# 150110_AriloTX_REV3_1_0_868MHZ_CORRECT_T.net
KiCad netlist of a schematic drawn in EAGLE
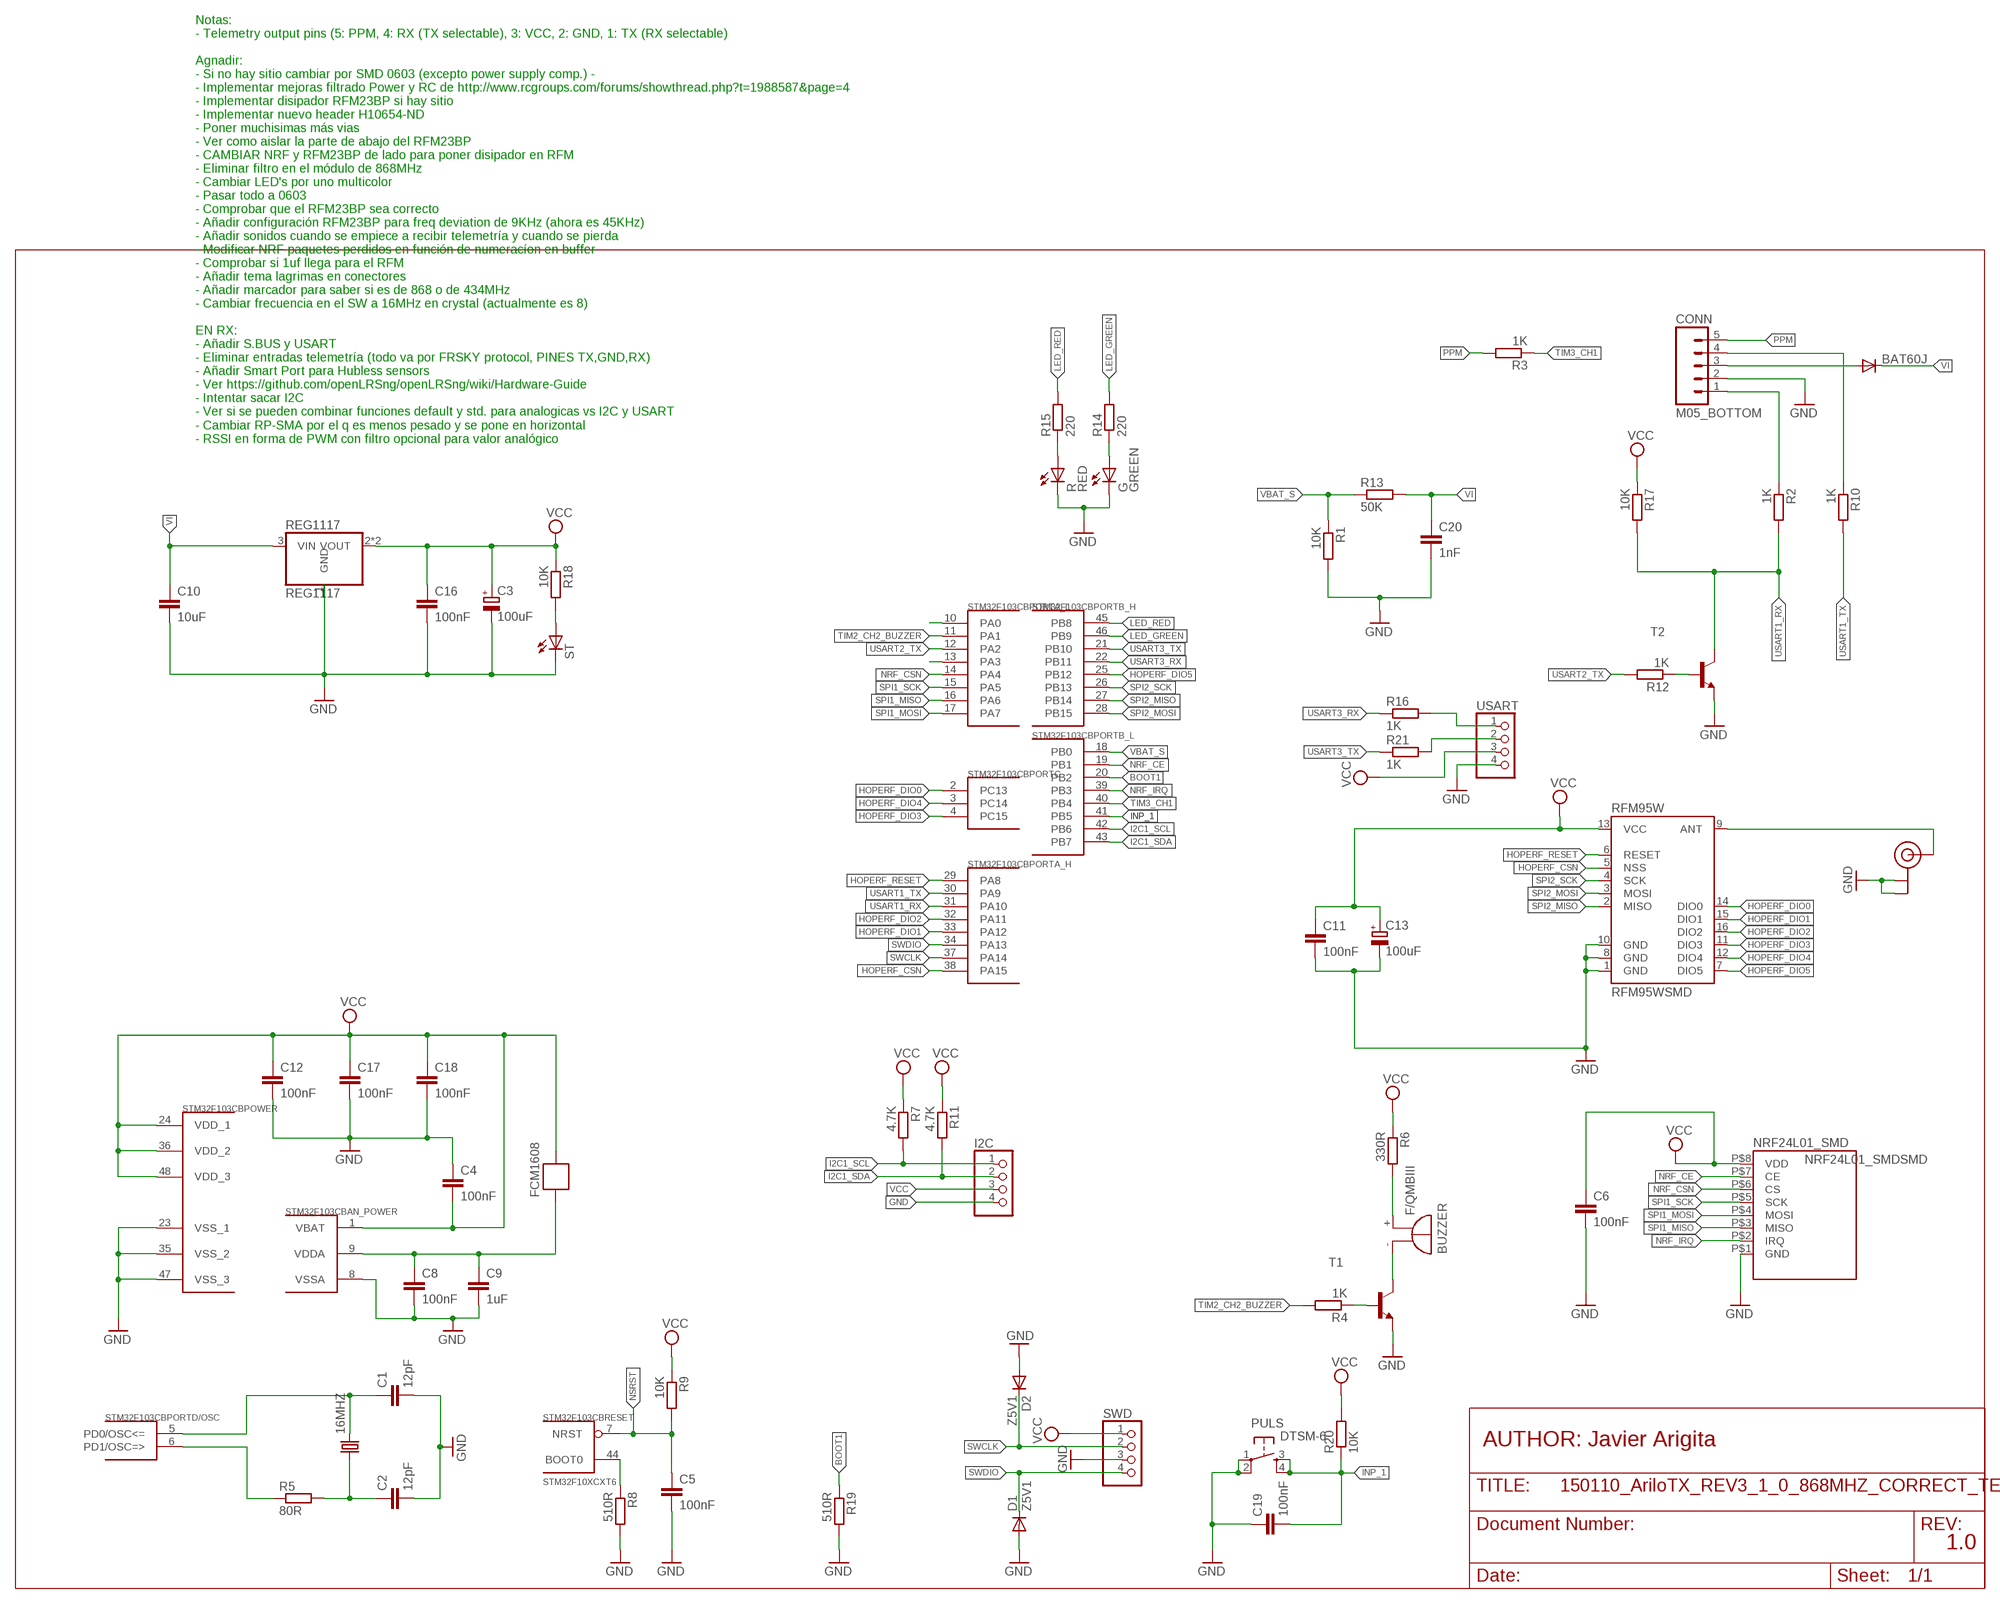
[diagram p0: schematic, sheet 1]

(export (version "E")
  (design (tool "Eeschema 10.0.6"))
  (components
    (comp (ref "16MHZ")
      (value "CRYSTAL5X3")
      (footprint "eagle-import:CRYSTAL-SMD-5X3")
      (libsource (lib "eagle-import") (part "CRYSTAL5X3"))
    )
    (comp (ref "BAT60J")
      (value "DIODE-SOD323-R")
      (footprint "eagle-import:SOD323-R")
      (libsource (lib "eagle-import") (part "DIODE-SOD323-R"))
    )
    (comp (ref "BUZZER")
      (value "F/QMBIII")
      (footprint "eagle-import:F_QMBIII")
      (libsource (lib "eagle-import") (part "F/QMBIII"))
    )
    (comp (ref "C1")
      (value "12pF")
      (footprint "eagle-import:C0603")
      (libsource (lib "eagle-import") (part "C-EUC0603"))
    )
    (comp (ref "C2")
      (value "12pF")
      (footprint "eagle-import:C0603")
      (libsource (lib "eagle-import") (part "C-EUC0603"))
    )
    (comp (ref "C3")
      (value "100uF")
      (footprint "eagle-import:SMC_B")
      (libsource (lib "eagle-import") (part "CPOL-EUSMCB"))
    )
    (comp (ref "C4")
      (value "100nF")
      (footprint "eagle-import:C0603")
      (libsource (lib "eagle-import") (part "C-EUC0603"))
    )
    (comp (ref "C5")
      (value "100nF")
      (footprint "eagle-import:C0603")
      (libsource (lib "eagle-import") (part "C-EUC0603"))
    )
    (comp (ref "C6")
      (value "100nF")
      (footprint "eagle-import:C0603")
      (libsource (lib "eagle-import") (part "C-EUC0603"))
    )
    (comp (ref "C8")
      (value "100nF")
      (footprint "eagle-import:C0603")
      (libsource (lib "eagle-import") (part "C-EUC0603"))
    )
    (comp (ref "C9")
      (value "1uF")
      (footprint "eagle-import:C0603")
      (libsource (lib "eagle-import") (part "C-EUC0603"))
    )
    (comp (ref "C10")
      (value "10uF")
      (footprint "eagle-import:C3216")
      (libsource (lib "eagle-import") (part "resistor_C-EUC3216"))
    )
    (comp (ref "C11")
      (value "100nF")
      (footprint "eagle-import:C0603")
      (libsource (lib "eagle-import") (part "C-EUC0603"))
    )
    (comp (ref "C12")
      (value "100nF")
      (footprint "eagle-import:C0603")
      (libsource (lib "eagle-import") (part "C-EUC0603"))
    )
    (comp (ref "C13")
      (value "100uF")
      (footprint "eagle-import:SMC_B")
      (libsource (lib "eagle-import") (part "CPOL-EUSMCB"))
    )
    (comp (ref "C16")
      (value "100nF")
      (footprint "eagle-import:C0603")
      (libsource (lib "eagle-import") (part "C-EUC0603"))
    )
    (comp (ref "C17")
      (value "100nF")
      (footprint "eagle-import:C0603")
      (libsource (lib "eagle-import") (part "C-EUC0603"))
    )
    (comp (ref "C18")
      (value "100nF")
      (footprint "eagle-import:C0603")
      (libsource (lib "eagle-import") (part "C-EUC0603"))
    )
    (comp (ref "C19")
      (value "100nF")
      (footprint "eagle-import:C0603")
      (libsource (lib "eagle-import") (part "C-EUC0603"))
    )
    (comp (ref "C20")
      (value "1nF")
      (footprint "eagle-import:C0603")
      (libsource (lib "eagle-import") (part "C-EUC0603"))
    )
    (comp (ref "CONN")
      (value "M05_BOTTOM")
      (footprint "eagle-import:M05_BOTTOM")
      (libsource (lib "eagle-import") (part "M05_BOTTOM"))
    )
    (comp (ref "D1")
      (value "Z5V1")
      (footprint "eagle-import:SOD323-R")
      (libsource (lib "eagle-import") (part "DIODE-SOD323-R"))
    )
    (comp (ref "D2")
      (value "Z5V1")
      (footprint "eagle-import:SOD323-R")
      (libsource (lib "eagle-import") (part "DIODE-SOD323-R"))
    )
    (comp (ref "FCM1608")
      (value "FERRITE-BEAD")
      (footprint "eagle-import:R0603")
      (libsource (lib "eagle-import") (part "FERRITE-BEAD"))
    )
    (comp (ref "G")
      (value "GREEN")
      (footprint "eagle-import:CHIP-LED0603")
      (libsource (lib "eagle-import") (part "LEDCHIP-LED0603"))
    )
    (comp (ref "I2C")
      (value "PINHD-1X4")
      (footprint "eagle-import:1X04")
      (libsource (lib "eagle-import") (part "PINHD-1X4"))
    )
    (comp (ref "NRF24L01_SMD")
      (value "NRF24L01_SMDSMD")
      (footprint "eagle-import:NRF24L01_SMD")
      (libsource (lib "eagle-import") (part "NRF24L01_SMDSMD"))
    )
    (comp (ref "PULS")
      (value "DTSM-6")
      (footprint "eagle-import:DTSM-6")
      (libsource (lib "eagle-import") (part "DTSM-6"))
    )
    (comp (ref "R")
      (value "RED")
      (footprint "eagle-import:CHIP-LED0603")
      (libsource (lib "eagle-import") (part "LEDCHIP-LED0603"))
    )
    (comp (ref "R1")
      (value "10K")
      (footprint "eagle-import:R0603")
      (libsource (lib "eagle-import") (part "R-EU_R0603"))
    )
    (comp (ref "R2")
      (value "1K")
      (footprint "eagle-import:R0603")
      (libsource (lib "eagle-import") (part "R-EU_R0603"))
    )
    (comp (ref "R3")
      (value "1K")
      (footprint "eagle-import:R0603")
      (libsource (lib "eagle-import") (part "R-EU_R0603"))
    )
    (comp (ref "R4")
      (value "1K")
      (footprint "eagle-import:R0603")
      (libsource (lib "eagle-import") (part "R-EU_R0603"))
    )
    (comp (ref "R5")
      (value "80R")
      (footprint "eagle-import:R0603")
      (libsource (lib "eagle-import") (part "R-EU_R0603"))
    )
    (comp (ref "R6")
      (value "330R")
      (footprint "eagle-import:R0603")
      (libsource (lib "eagle-import") (part "R-EU_R0603"))
    )
    (comp (ref "R7")
      (value "4.7K")
      (footprint "eagle-import:R0603")
      (libsource (lib "eagle-import") (part "R-EU_R0603"))
    )
    (comp (ref "R8")
      (value "510R")
      (footprint "eagle-import:R0603")
      (libsource (lib "eagle-import") (part "R-EU_R0603"))
    )
    (comp (ref "R9")
      (value "10K")
      (footprint "eagle-import:R0603")
      (libsource (lib "eagle-import") (part "R-EU_R0603"))
    )
    (comp (ref "R10")
      (value "1K")
      (footprint "eagle-import:R0603")
      (libsource (lib "eagle-import") (part "R-EU_R0603"))
    )
    (comp (ref "R11")
      (value "4.7K")
      (footprint "eagle-import:R0603")
      (libsource (lib "eagle-import") (part "R-EU_R0603"))
    )
    (comp (ref "R12")
      (value "1K")
      (footprint "eagle-import:R0603")
      (libsource (lib "eagle-import") (part "R-EU_R0603"))
    )
    (comp (ref "R13")
      (value "50K")
      (footprint "eagle-import:R0603")
      (libsource (lib "eagle-import") (part "R-EU_R0603"))
    )
    (comp (ref "R14")
      (value "220")
      (footprint "eagle-import:R0603")
      (libsource (lib "eagle-import") (part "R-EU_R0603"))
    )
    (comp (ref "R15")
      (value "220")
      (footprint "eagle-import:R0603")
      (libsource (lib "eagle-import") (part "R-EU_R0603"))
    )
    (comp (ref "R16")
      (value "1K")
      (footprint "eagle-import:R0603")
      (libsource (lib "eagle-import") (part "R-EU_R0603"))
    )
    (comp (ref "R17")
      (value "10K")
      (footprint "eagle-import:R0603")
      (libsource (lib "eagle-import") (part "R-EU_R0603"))
    )
    (comp (ref "R18")
      (value "10K")
      (footprint "eagle-import:R0603")
      (libsource (lib "eagle-import") (part "R-EU_R0603"))
    )
    (comp (ref "R19")
      (value "510R")
      (footprint "eagle-import:R0603")
      (libsource (lib "eagle-import") (part "R-EU_R0603"))
    )
    (comp (ref "R20")
      (value "10K")
      (footprint "eagle-import:R0603")
      (libsource (lib "eagle-import") (part "R-EU_R0603"))
    )
    (comp (ref "R21")
      (value "1K")
      (footprint "eagle-import:R0603")
      (libsource (lib "eagle-import") (part "R-EU_R0603"))
    )
    (comp (ref "REG1117")
      (value "REG1117")
      (footprint "eagle-import:SOT223")
      (libsource (lib "eagle-import") (part "REG1117"))
    )
    (comp (ref "RFM95W")
      (value "RFM95WSMD")
      (footprint "eagle-import:MISIEK_RFM95W_SMD")
      (libsource (lib "eagle-import") (part "MISIEK_RFM95WSMD"))
    )
    (comp (ref "ST")
      (value "LEDCHIP-LED0603")
      (footprint "eagle-import:CHIP-LED0603")
      (libsource (lib "eagle-import") (part "LEDCHIP-LED0603"))
    )
    (comp (ref "STM32F103CB")
      (value "STM32F10XCXT6")
      (footprint "eagle-import:TQFP48")
      (libsource (lib "eagle-import") (part "STM32F10XCXT6"))
    )
    (comp (ref "SWD")
      (value "PINHD-1X4")
      (footprint "eagle-import:1X04")
      (libsource (lib "eagle-import") (part "PINHD-1X4"))
    )
    (comp (ref "T1")
      (value "BC848-NPN-SOT23-BEC")
      (footprint "eagle-import:SOT23-BEC")
      (libsource (lib "eagle-import") (part "-NPN-SOT23-BECBC848"))
    )
    (comp (ref "T2")
      (value "BC848-NPN-SOT23-BEC")
      (footprint "eagle-import:SOT23-BEC")
      (libsource (lib "eagle-import") (part "-NPN-SOT23-BECBC848"))
    )
    (comp (ref "U.FL")
      (value "U.FL")
      (footprint "eagle-import:U.FL")
      (libsource (lib "eagle-import") (part "U.FL"))
    )
    (comp (ref "USART")
      (value "PINHD-1X4")
      (footprint "eagle-import:1X04")
      (libsource (lib "eagle-import") (part "PINHD-1X4"))
    )
  )
  (nets
    (net (code "1") (name "BOOT1") (class "Default")
      (node (ref "R19") (pin "1") (pinfunction "1_1") (pintype "passive"))
      (node (ref "STM32F103CB") (pin "20") (pinfunction "PB2_20") (pintype "bidirectional"))
    )
    (net (code "2") (name "GND") (class "Default")
      (node (ref "C1") (pin "2") (pinfunction "2_2") (pintype "passive"))
      (node (ref "C10") (pin "2") (pinfunction "2_2") (pintype "passive"))
      (node (ref "C11") (pin "2") (pinfunction "2_2") (pintype "passive"))
      (node (ref "C12") (pin "2") (pinfunction "2_2") (pintype "passive"))
      (node (ref "C13") (pin "-") (pinfunction "-_-") (pintype "passive"))
      (node (ref "C16") (pin "2") (pinfunction "2_2") (pintype "passive"))
      (node (ref "C17") (pin "2") (pinfunction "2_2") (pintype "passive"))
      (node (ref "C18") (pin "2") (pinfunction "2_2") (pintype "passive"))
      (node (ref "C19") (pin "1") (pinfunction "1_1") (pintype "passive"))
      (node (ref "C2") (pin "2") (pinfunction "2_2") (pintype "passive"))
      (node (ref "C20") (pin "2") (pinfunction "2_2") (pintype "passive"))
      (node (ref "C3") (pin "-") (pinfunction "-_-") (pintype "passive"))
      (node (ref "C4") (pin "1") (pinfunction "1_1") (pintype "passive"))
      (node (ref "C5") (pin "2") (pinfunction "2_2") (pintype "passive"))
      (node (ref "C6") (pin "2") (pinfunction "2_2") (pintype "passive"))
      (node (ref "C8") (pin "2") (pinfunction "2_2") (pintype "passive"))
      (node (ref "C9") (pin "2") (pinfunction "2_2") (pintype "passive"))
      (node (ref "CONN") (pin "2") (pinfunction "2_2") (pintype "passive"))
      (node (ref "D1") (pin "A") (pinfunction "A_A") (pintype "passive"))
      (node (ref "D2") (pin "A") (pinfunction "A_A") (pintype "passive"))
      (node (ref "G") (pin "C") (pinfunction "C_C") (pintype "passive"))
      (node (ref "I2C") (pin "4") (pinfunction "4_4") (pintype "passive"))
      (node (ref "NRF24L01_SMD") (pin "P$1") (pinfunction "GND_P$1") (pintype "power_in"))
      (node (ref "PULS") (pin "1") (pinfunction "1_1") (pintype "passive"))
      (node (ref "PULS") (pin "2") (pinfunction "2_2") (pintype "passive"))
      (node (ref "R") (pin "C") (pinfunction "C_C") (pintype "passive"))
      (node (ref "R1") (pin "2") (pinfunction "2_2") (pintype "passive"))
      (node (ref "R19") (pin "2") (pinfunction "2_2") (pintype "passive"))
      (node (ref "R8") (pin "2") (pinfunction "2_2") (pintype "passive"))
      (node (ref "REG1117") (pin "1") (pinfunction "GND_1") (pintype "power_in"))
      (node (ref "RFM95W") (pin "1") (pinfunction "GND_1") (pintype "power_in"))
      (node (ref "RFM95W") (pin "10") (pinfunction "GND_10") (pintype "power_in"))
      (node (ref "RFM95W") (pin "8") (pinfunction "GND_8") (pintype "power_in"))
      (node (ref "ST") (pin "C") (pinfunction "C_C") (pintype "passive"))
      (node (ref "STM32F103CB") (pin "23") (pinfunction "VSS_1_23") (pintype "power_in"))
      (node (ref "STM32F103CB") (pin "35") (pinfunction "VSS_2_35") (pintype "power_in"))
      (node (ref "STM32F103CB") (pin "47") (pinfunction "VSS_3_47") (pintype "power_in"))
      (node (ref "STM32F103CB") (pin "8") (pinfunction "VSSA_8") (pintype "power_in"))
      (node (ref "SWD") (pin "3") (pinfunction "3_3") (pintype "passive"))
      (node (ref "T1") (pin "E") (pinfunction "E_E") (pintype "passive"))
      (node (ref "T2") (pin "E") (pinfunction "E_E") (pintype "passive"))
      (node (ref "U.FL") (pin "P$1") (pinfunction "GND_P$1") (pintype "bidirectional"))
      (node (ref "U.FL") (pin "P$2") (pinfunction "GND_P$2") (pintype "bidirectional"))
      (node (ref "USART") (pin "4") (pinfunction "4_4") (pintype "passive"))
    )
    (net (code "3") (name "HOPERF_CSN") (class "Default")
      (node (ref "RFM95W") (pin "5") (pinfunction "NSS_5") (pintype "input"))
      (node (ref "STM32F103CB") (pin "38") (pinfunction "PA15_38") (pintype "bidirectional"))
    )
    (net (code "4") (name "HOPERF_DIO0") (class "Default")
      (node (ref "RFM95W") (pin "14") (pinfunction "DIO0_14") (pintype "input"))
      (node (ref "STM32F103CB") (pin "2") (pinfunction "PC13_2") (pintype "bidirectional"))
    )
    (net (code "5") (name "HOPERF_DIO1") (class "Default")
      (node (ref "RFM95W") (pin "15") (pinfunction "DIO1_15") (pintype "input"))
      (node (ref "STM32F103CB") (pin "33") (pinfunction "PA12_33") (pintype "bidirectional"))
    )
    (net (code "6") (name "HOPERF_DIO2") (class "Default")
      (node (ref "RFM95W") (pin "16") (pinfunction "DIO2_16") (pintype "input"))
      (node (ref "STM32F103CB") (pin "32") (pinfunction "PA11_32") (pintype "bidirectional"))
    )
    (net (code "7") (name "HOPERF_DIO3") (class "Default")
      (node (ref "RFM95W") (pin "11") (pinfunction "DIO3_11") (pintype "bidirectional"))
      (node (ref "STM32F103CB") (pin "4") (pinfunction "PC15_4") (pintype "bidirectional"))
    )
    (net (code "8") (name "HOPERF_DIO4") (class "Default")
      (node (ref "RFM95W") (pin "12") (pinfunction "DIO4_12") (pintype "bidirectional"))
      (node (ref "STM32F103CB") (pin "3") (pinfunction "PC14_3") (pintype "bidirectional"))
    )
    (net (code "9") (name "HOPERF_DIO5") (class "Default")
      (node (ref "RFM95W") (pin "7") (pinfunction "DIO5_7") (pintype "bidirectional"))
      (node (ref "STM32F103CB") (pin "25") (pinfunction "PB12_25") (pintype "bidirectional"))
    )
    (net (code "10") (name "HOPERF_RESET") (class "Default")
      (node (ref "RFM95W") (pin "6") (pinfunction "RESET_6") (pintype "output"))
      (node (ref "STM32F103CB") (pin "29") (pinfunction "PA8_29") (pintype "bidirectional"))
    )
    (net (code "11") (name "I2C1_SCL") (class "Default")
      (node (ref "I2C") (pin "1") (pinfunction "1_1") (pintype "passive"))
      (node (ref "R7") (pin "2") (pinfunction "2_2") (pintype "passive"))
      (node (ref "STM32F103CB") (pin "42") (pinfunction "PB6_42") (pintype "bidirectional"))
    )
    (net (code "12") (name "I2C1_SDA") (class "Default")
      (node (ref "I2C") (pin "2") (pinfunction "2_2") (pintype "passive"))
      (node (ref "R11") (pin "2") (pinfunction "2_2") (pintype "passive"))
      (node (ref "STM32F103CB") (pin "43") (pinfunction "PB7_43") (pintype "bidirectional"))
    )
    (net (code "13") (name "INP_1") (class "Default")
      (node (ref "C19") (pin "2") (pinfunction "2_2") (pintype "passive"))
      (node (ref "PULS") (pin "3") (pinfunction "3_3") (pintype "passive"))
      (node (ref "PULS") (pin "4") (pinfunction "4_4") (pintype "passive"))
      (node (ref "R20") (pin "1") (pinfunction "1_1") (pintype "passive"))
      (node (ref "STM32F103CB") (pin "41") (pinfunction "PB5_41") (pintype "bidirectional"))
    )
    (net (code "14") (name "LED_GREEN") (class "Default")
      (node (ref "R14") (pin "2") (pinfunction "2_2") (pintype "passive"))
      (node (ref "STM32F103CB") (pin "46") (pinfunction "PB9_46") (pintype "bidirectional"))
    )
    (net (code "15") (name "LED_RED") (class "Default")
      (node (ref "R15") (pin "2") (pinfunction "2_2") (pintype "passive"))
      (node (ref "STM32F103CB") (pin "45") (pinfunction "PB8_45") (pintype "bidirectional"))
    )
    (net (code "16") (name "NRF_CE") (class "Default")
      (node (ref "NRF24L01_SMD") (pin "P$7") (pinfunction "CE_P$7") (pintype "input"))
      (node (ref "STM32F103CB") (pin "19") (pinfunction "PB1_19") (pintype "bidirectional"))
    )
    (net (code "17") (name "NRF_CSN") (class "Default")
      (node (ref "NRF24L01_SMD") (pin "P$6") (pinfunction "CS_P$6") (pintype "input"))
      (node (ref "STM32F103CB") (pin "14") (pinfunction "PA4_14") (pintype "bidirectional"))
    )
    (net (code "18") (name "NRF_IRQ") (class "Default")
      (node (ref "NRF24L01_SMD") (pin "P$2") (pinfunction "IRQ_P$2") (pintype "output"))
      (node (ref "STM32F103CB") (pin "39") (pinfunction "PB3_39") (pintype "bidirectional"))
    )
    (net (code "19") (name "NSRST") (class "Default")
      (node (ref "C5") (pin "1") (pinfunction "1_1") (pintype "passive"))
      (node (ref "R9") (pin "2") (pinfunction "2_2") (pintype "passive"))
      (node (ref "STM32F103CB") (pin "7") (pinfunction "NRST_7") (pintype "input"))
    )
    (net (code "20") (name "Net-(16MHZ-2)") (class "Default")
      (node (ref "16MHZ") (pin "3") (pinfunction "2_3") (pintype "passive"))
      (node (ref "C1") (pin "1") (pinfunction "1_1") (pintype "passive"))
      (node (ref "STM32F103CB") (pin "5") (pinfunction "PD0/OSC<=_5") (pintype "bidirectional"))
    )
    (net (code "21") (name "Net-(16MHZ-Pad1)") (class "Default")
      (node (ref "16MHZ") (pin "1") (pinfunction "1_1") (pintype "passive"))
      (node (ref "C2") (pin "1") (pinfunction "1_1") (pintype "passive"))
      (node (ref "R5") (pin "2") (pinfunction "2_2") (pintype "passive"))
    )
    (net (code "22") (name "Net-(BAT60J-PadA)") (class "Default")
      (node (ref "BAT60J") (pin "A") (pinfunction "A_A") (pintype "passive"))
      (node (ref "CONN") (pin "3") (pinfunction "3_3") (pintype "passive"))
    )
    (net (code "23") (name "Net-(BUZZER-+)") (class "Default")
      (node (ref "BUZZER") (pin "-") (pinfunction "+_-") (pintype "passive"))
      (node (ref "T1") (pin "C") (pinfunction "C_C") (pintype "passive"))
    )
    (net (code "24") (name "Net-(BUZZER--)") (class "Default")
      (node (ref "BUZZER") (pin "+") (pinfunction "-_+") (pintype "passive"))
      (node (ref "R6") (pin "2") (pinfunction "2_2") (pintype "passive"))
    )
    (net (code "25") (name "Net-(CONN-Pad1)") (class "Default")
      (node (ref "CONN") (pin "1") (pinfunction "1_1") (pintype "passive"))
      (node (ref "R2") (pin "1") (pinfunction "1_1") (pintype "passive"))
    )
    (net (code "26") (name "Net-(CONN-Pad4)") (class "Default")
      (node (ref "CONN") (pin "4") (pinfunction "4_4") (pintype "passive"))
      (node (ref "R10") (pin "1") (pinfunction "1_1") (pintype "passive"))
    )
    (net (code "27") (name "Net-(FCM1608-P$2)") (class "Default")
      (node (ref "C8") (pin "1") (pinfunction "1_1") (pintype "passive"))
      (node (ref "C9") (pin "1") (pinfunction "1_1") (pintype "passive"))
      (node (ref "FCM1608") (pin "2") (pinfunction "P$2_2") (pintype "bidirectional"))
      (node (ref "STM32F103CB") (pin "9") (pinfunction "VDDA_9") (pintype "power_in"))
    )
    (net (code "28") (name "Net-(G-PadA)") (class "Default")
      (node (ref "G") (pin "A") (pinfunction "A_A") (pintype "passive"))
      (node (ref "R14") (pin "1") (pinfunction "1_1") (pintype "passive"))
    )
    (net (code "29") (name "Net-(R-PadA)") (class "Default")
      (node (ref "R") (pin "A") (pinfunction "A_A") (pintype "passive"))
      (node (ref "R15") (pin "1") (pinfunction "1_1") (pintype "passive"))
    )
    (net (code "30") (name "Net-(R4-Pad1)") (class "Default")
      (node (ref "R4") (pin "1") (pinfunction "1_1") (pintype "passive"))
      (node (ref "T1") (pin "B") (pinfunction "B_B") (pintype "passive"))
    )
    (net (code "31") (name "Net-(R12-Pad1)") (class "Default")
      (node (ref "R12") (pin "1") (pinfunction "1_1") (pintype "passive"))
      (node (ref "T2") (pin "B") (pinfunction "B_B") (pintype "passive"))
    )
    (net (code "32") (name "Net-(R16-Pad2)") (class "Default")
      (node (ref "R16") (pin "2") (pinfunction "2_2") (pintype "passive"))
      (node (ref "USART") (pin "1") (pinfunction "1_1") (pintype "passive"))
    )
    (net (code "33") (name "Net-(R18-Pad2)") (class "Default")
      (node (ref "R18") (pin "2") (pinfunction "2_2") (pintype "passive"))
      (node (ref "ST") (pin "A") (pinfunction "A_A") (pintype "passive"))
    )
    (net (code "34") (name "Net-(R21-Pad2)") (class "Default")
      (node (ref "R21") (pin "2") (pinfunction "2_2") (pintype "passive"))
      (node (ref "USART") (pin "2") (pinfunction "2_2") (pintype "passive"))
    )
    (net (code "35") (name "Net-(RFM95W-ANT)") (class "Default")
      (node (ref "RFM95W") (pin "9") (pinfunction "ANT_9") (pintype "bidirectional"))
      (node (ref "U.FL") (pin "P$3") (pinfunction "SIGNAL_P$3") (pintype "bidirectional"))
    )
    (net (code "36") (name "Net-(STM32F103CBG-PD1{slash}OSC=>)") (class "Default")
      (node (ref "R5") (pin "1") (pinfunction "1_1") (pintype "passive"))
      (node (ref "STM32F103CB") (pin "6") (pinfunction "PD1/OSC=>_6") (pintype "bidirectional"))
    )
    (net (code "37") (name "Net-(STM32F103CBI-BOOT0)") (class "Default")
      (node (ref "R8") (pin "1") (pinfunction "1_1") (pintype "passive"))
      (node (ref "STM32F103CB") (pin "44") (pinfunction "BOOT0_44") (pintype "input"))
    )
    (net (code "38") (name "PPM") (class "Default")
      (node (ref "CONN") (pin "5") (pinfunction "5_5") (pintype "passive"))
      (node (ref "R3") (pin "2") (pinfunction "2_2") (pintype "passive"))
    )
    (net (code "39") (name "SPI1_MISO") (class "Default")
      (node (ref "NRF24L01_SMD") (pin "P$3") (pinfunction "MISO_P$3") (pintype "output"))
      (node (ref "STM32F103CB") (pin "16") (pinfunction "PA6_16") (pintype "bidirectional"))
    )
    (net (code "40") (name "SPI1_MOSI") (class "Default")
      (node (ref "NRF24L01_SMD") (pin "P$4") (pinfunction "MOSI_P$4") (pintype "input"))
      (node (ref "STM32F103CB") (pin "17") (pinfunction "PA7_17") (pintype "bidirectional"))
    )
    (net (code "41") (name "SPI1_SCK") (class "Default")
      (node (ref "NRF24L01_SMD") (pin "P$5") (pinfunction "SCK_P$5") (pintype "input"))
      (node (ref "STM32F103CB") (pin "15") (pinfunction "PA5_15") (pintype "bidirectional"))
    )
    (net (code "42") (name "SPI2_MISO") (class "Default")
      (node (ref "RFM95W") (pin "2") (pinfunction "MISO_2") (pintype "output"))
      (node (ref "STM32F103CB") (pin "27") (pinfunction "PB14_27") (pintype "bidirectional"))
    )
    (net (code "43") (name "SPI2_MOSI") (class "Default")
      (node (ref "RFM95W") (pin "3") (pinfunction "MOSI_3") (pintype "input"))
      (node (ref "STM32F103CB") (pin "28") (pinfunction "PB15_28") (pintype "bidirectional"))
    )
    (net (code "44") (name "SPI2_SCK") (class "Default")
      (node (ref "RFM95W") (pin "4") (pinfunction "SCK_4") (pintype "input"))
      (node (ref "STM32F103CB") (pin "26") (pinfunction "PB13_26") (pintype "bidirectional"))
    )
    (net (code "45") (name "SWCLK") (class "Default")
      (node (ref "D2") (pin "C") (pinfunction "C_C") (pintype "passive"))
      (node (ref "STM32F103CB") (pin "37") (pinfunction "PA14_37") (pintype "bidirectional"))
      (node (ref "SWD") (pin "2") (pinfunction "2_2") (pintype "passive"))
    )
    (net (code "46") (name "SWDIO") (class "Default")
      (node (ref "D1") (pin "C") (pinfunction "C_C") (pintype "passive"))
      (node (ref "STM32F103CB") (pin "34") (pinfunction "PA13_34") (pintype "bidirectional"))
      (node (ref "SWD") (pin "4") (pinfunction "4_4") (pintype "passive"))
    )
    (net (code "47") (name "TIM2_CH2_BUZZER") (class "Default")
      (node (ref "R4") (pin "2") (pinfunction "2_2") (pintype "passive"))
      (node (ref "STM32F103CB") (pin "11") (pinfunction "PA1_11") (pintype "bidirectional"))
    )
    (net (code "48") (name "TIM3_CH1") (class "Default")
      (node (ref "R3") (pin "1") (pinfunction "1_1") (pintype "passive"))
      (node (ref "STM32F103CB") (pin "40") (pinfunction "PB4_40") (pintype "bidirectional"))
    )
    (net (code "49") (name "USART1_RX") (class "Default")
      (node (ref "R17") (pin "2") (pinfunction "2_2") (pintype "passive"))
      (node (ref "R2") (pin "2") (pinfunction "2_2") (pintype "passive"))
      (node (ref "STM32F103CB") (pin "31") (pinfunction "PA10_31") (pintype "bidirectional"))
      (node (ref "T2") (pin "C") (pinfunction "C_C") (pintype "passive"))
    )
    (net (code "50") (name "USART1_TX") (class "Default")
      (node (ref "R10") (pin "2") (pinfunction "2_2") (pintype "passive"))
      (node (ref "STM32F103CB") (pin "30") (pinfunction "PA9_30") (pintype "bidirectional"))
    )
    (net (code "51") (name "USART2_TX") (class "Default")
      (node (ref "R12") (pin "2") (pinfunction "2_2") (pintype "passive"))
      (node (ref "STM32F103CB") (pin "12") (pinfunction "PA2_12") (pintype "bidirectional"))
    )
    (net (code "52") (name "USART3_RX") (class "Default")
      (node (ref "R16") (pin "1") (pinfunction "1_1") (pintype "passive"))
      (node (ref "STM32F103CB") (pin "22") (pinfunction "PB11_22") (pintype "bidirectional"))
    )
    (net (code "53") (name "USART3_TX") (class "Default")
      (node (ref "R21") (pin "1") (pinfunction "1_1") (pintype "passive"))
      (node (ref "STM32F103CB") (pin "21") (pinfunction "PB10_21") (pintype "bidirectional"))
    )
    (net (code "54") (name "VBAT_S") (class "Default")
      (node (ref "R1") (pin "1") (pinfunction "1_1") (pintype "passive"))
      (node (ref "R13") (pin "1") (pinfunction "1_1") (pintype "passive"))
      (node (ref "STM32F103CB") (pin "18") (pinfunction "PB0_18") (pintype "bidirectional"))
    )
    (net (code "55") (name "VCC") (class "Default")
      (node (ref "C11") (pin "1") (pinfunction "1_1") (pintype "passive"))
      (node (ref "C12") (pin "1") (pinfunction "1_1") (pintype "passive"))
      (node (ref "C13") (pin "+") (pinfunction "+_+") (pintype "passive"))
      (node (ref "C16") (pin "1") (pinfunction "1_1") (pintype "passive"))
      (node (ref "C17") (pin "1") (pinfunction "1_1") (pintype "passive"))
      (node (ref "C18") (pin "1") (pinfunction "1_1") (pintype "passive"))
      (node (ref "C3") (pin "+") (pinfunction "+_+") (pintype "passive"))
      (node (ref "C4") (pin "2") (pinfunction "2_2") (pintype "passive"))
      (node (ref "C6") (pin "1") (pinfunction "1_1") (pintype "passive"))
      (node (ref "FCM1608") (pin "1") (pinfunction "P$1_1") (pintype "bidirectional"))
      (node (ref "I2C") (pin "3") (pinfunction "3_3") (pintype "passive"))
      (node (ref "NRF24L01_SMD") (pin "P$8") (pinfunction "VDD_P$8") (pintype "bidirectional"))
      (node (ref "R11") (pin "1") (pinfunction "1_1") (pintype "passive"))
      (node (ref "R17") (pin "1") (pinfunction "1_1") (pintype "passive"))
      (node (ref "R18") (pin "1") (pinfunction "1_1") (pintype "passive"))
      (node (ref "R20") (pin "2") (pinfunction "2_2") (pintype "passive"))
      (node (ref "R6") (pin "1") (pinfunction "1_1") (pintype "passive"))
      (node (ref "R7") (pin "1") (pinfunction "1_1") (pintype "passive"))
      (node (ref "R9") (pin "1") (pinfunction "1_1") (pintype "passive"))
      (node (ref "REG1117") (pin "2") (pinfunction "VOUT_2") (pintype "power_in"))
      (node (ref "REG1117") (pin "4") (pinfunction "VOUT_4") (pintype "power_in"))
      (node (ref "RFM95W") (pin "13") (pinfunction "VCC_13") (pintype "bidirectional"))
      (node (ref "STM32F103CB") (pin "1") (pinfunction "VBAT_1") (pintype "power_in"))
      (node (ref "STM32F103CB") (pin "24") (pinfunction "VDD_1_24") (pintype "power_in"))
      (node (ref "STM32F103CB") (pin "36") (pinfunction "VDD_2_36") (pintype "power_in"))
      (node (ref "STM32F103CB") (pin "48") (pinfunction "VDD_3_48") (pintype "power_in"))
      (node (ref "SWD") (pin "1") (pinfunction "1_1") (pintype "passive"))
      (node (ref "USART") (pin "3") (pinfunction "3_3") (pintype "passive"))
    )
    (net (code "56") (name "VI") (class "Default")
      (node (ref "BAT60J") (pin "C") (pinfunction "C_C") (pintype "passive"))
      (node (ref "C10") (pin "1") (pinfunction "1_1") (pintype "passive"))
      (node (ref "C20") (pin "1") (pinfunction "1_1") (pintype "passive"))
      (node (ref "R13") (pin "2") (pinfunction "2_2") (pintype "passive"))
      (node (ref "REG1117") (pin "3") (pinfunction "VIN_3") (pintype "input"))
    )
    (net (code "57") (name "unconnected-(STM32F103CBC-PA0-Pad10)") (class "Default")
      (node (ref "STM32F103CB") (pin "10") (pinfunction "PA0_10") (pintype "bidirectional"))
    )
    (net (code "58") (name "unconnected-(STM32F103CBC-PA3-Pad13)") (class "Default")
      (node (ref "STM32F103CB") (pin "13") (pinfunction "PA3_13") (pintype "bidirectional"))
    )
  )
)
